# Proiect_TSC_v48.net
KiCad netlist of a schematic drawn in EAGLE
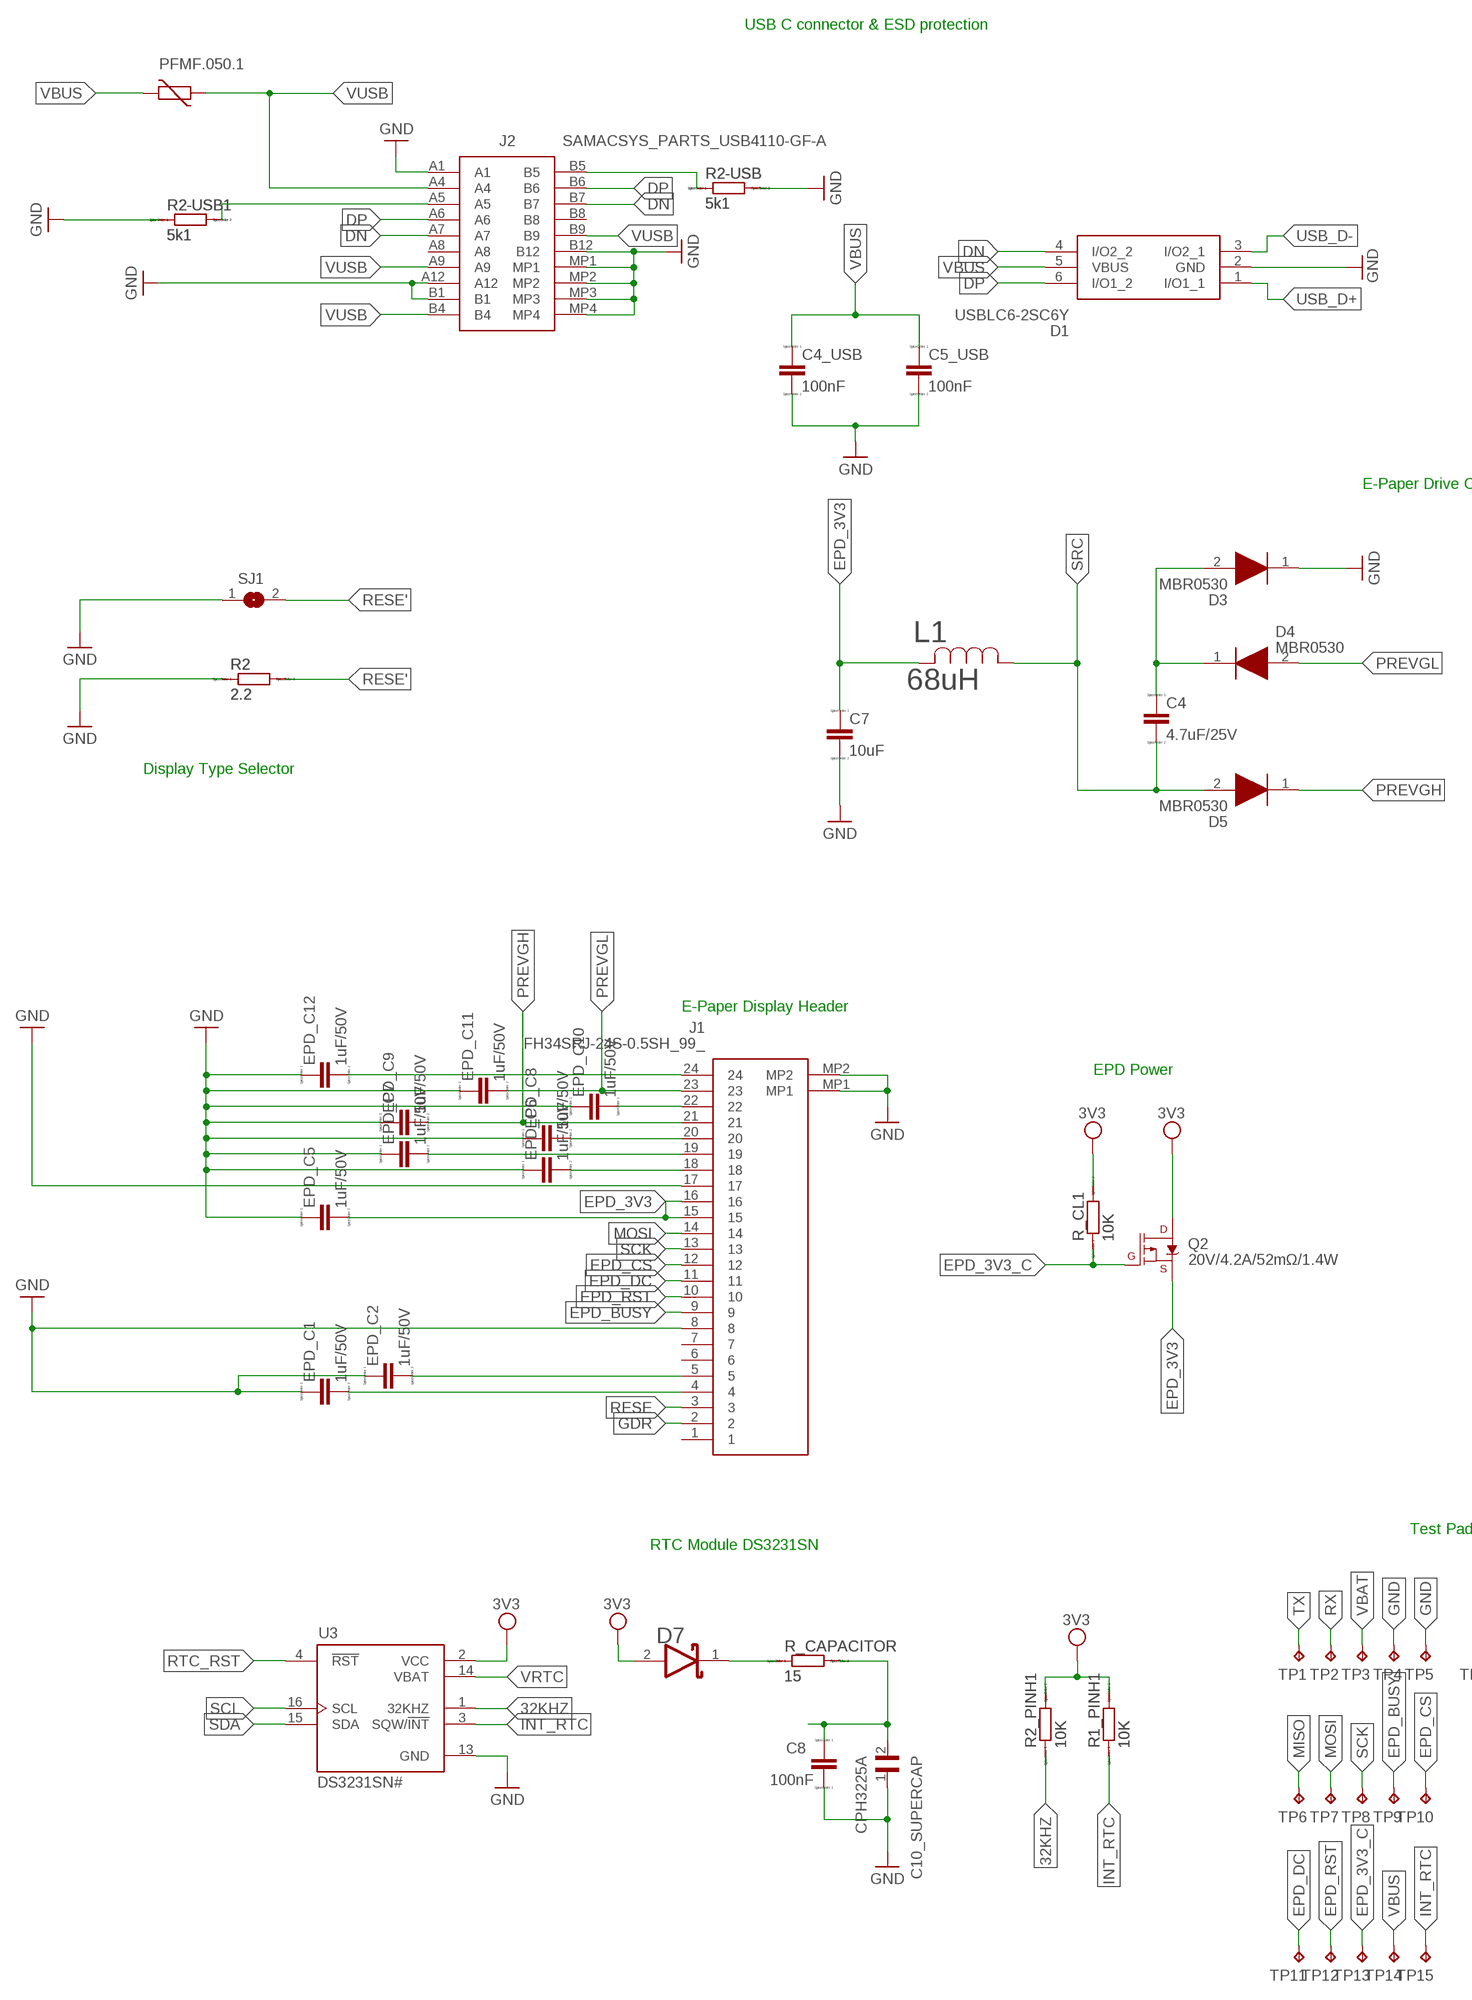
[diagram p0: schematic, sheet 1, part 1 of 2]
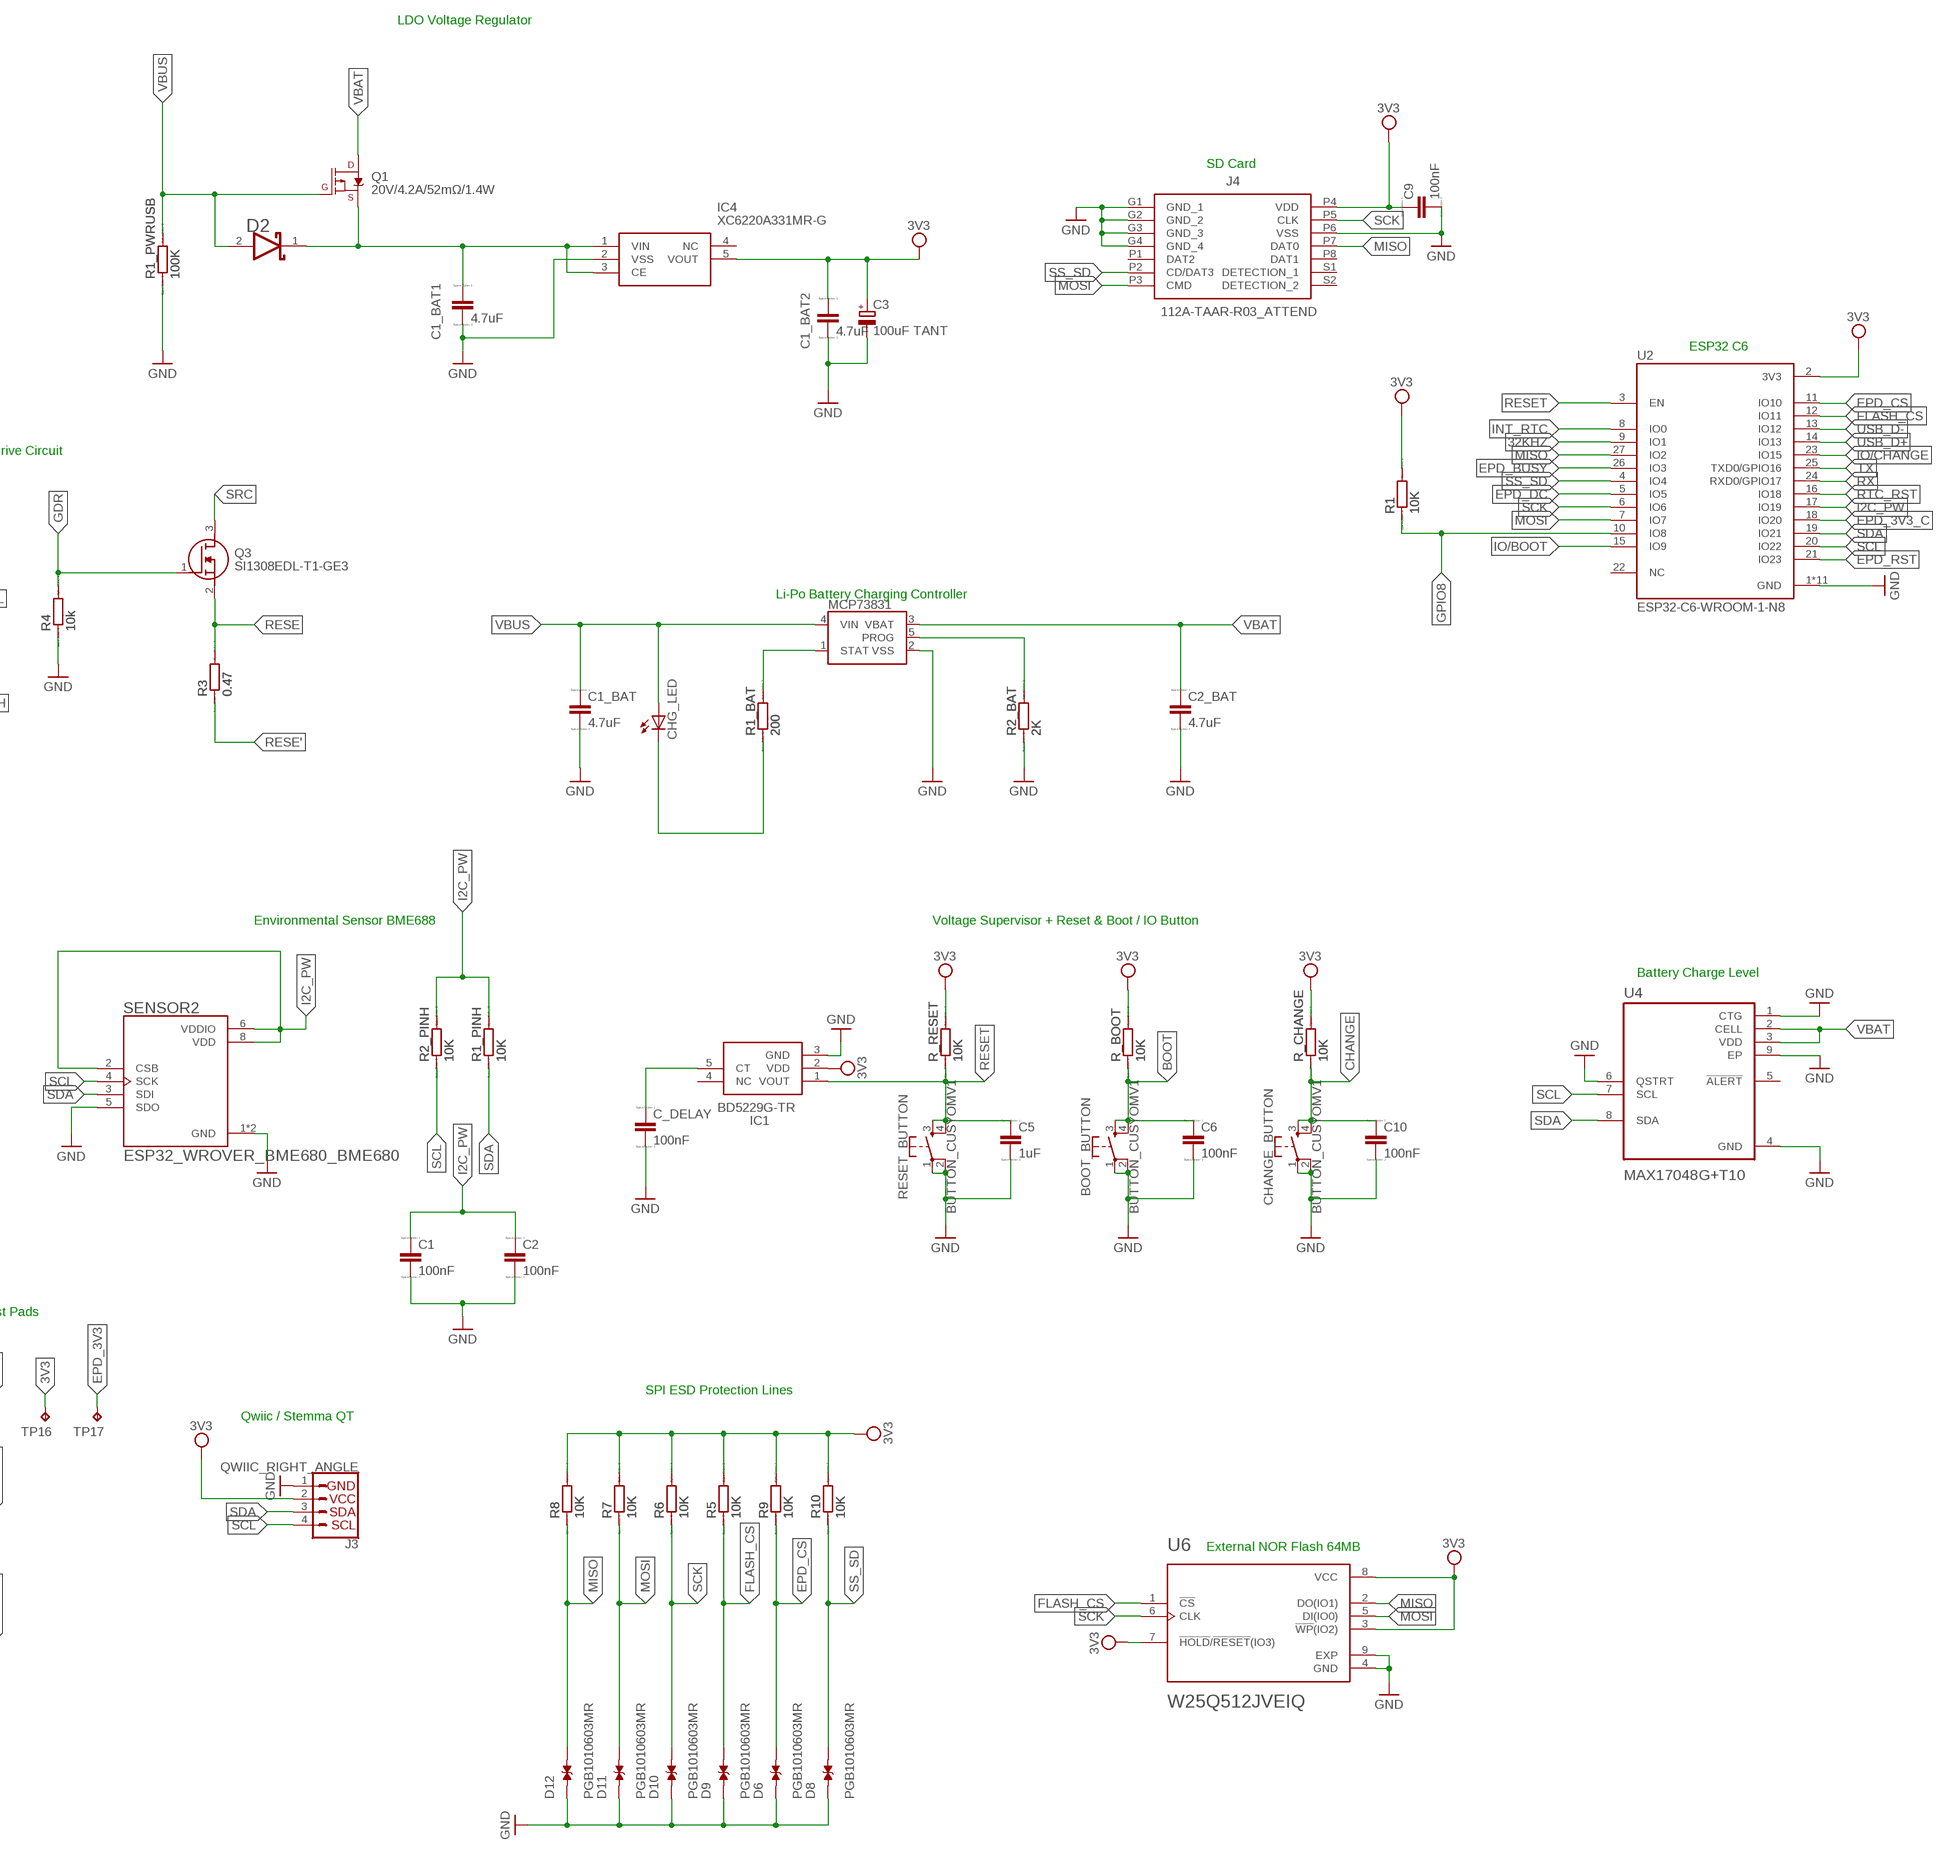
[diagram p1: schematic, sheet 1, part 2 of 2]

(export (version "E")
  (design (tool "Eeschema 10.0.6"))
  (components
    (comp (ref "BOOT_BUTTON")
      (value "BUTTON_CUSYOMV1")
      (footprint "eagle-import:MYBUTTON")
      (libsource (lib "eagle-import") (part "BUTTON_CUSYOMV1"))
    )
    (comp (ref "C1")
      (value "100nF")
      (footprint "eagle-import:ESP32_WROVER_EAGLE-LTSPICE_C0402")
      (libsource (lib "eagle-import") (part "ESP32_WROVER_EAGLE-LTSPICE_CC0402"))
    )
    (comp (ref "C1_BAT")
      (value "4.7uF")
      (footprint "eagle-import:ESP32_WROVER_EAGLE-LTSPICE_C0402")
      (libsource (lib "eagle-import") (part "ESP32_WROVER_EAGLE-LTSPICE_CC0402"))
    )
    (comp (ref "C1_BAT1")
      (value "4.7uF")
      (footprint "eagle-import:ESP32_WROVER_EAGLE-LTSPICE_C0402")
      (libsource (lib "eagle-import") (part "ESP32_WROVER_EAGLE-LTSPICE_CC0402"))
    )
    (comp (ref "C1_BAT2")
      (value "4.7uF")
      (footprint "eagle-import:ESP32_WROVER_EAGLE-LTSPICE_C0402")
      (libsource (lib "eagle-import") (part "ESP32_WROVER_EAGLE-LTSPICE_CC0402"))
    )
    (comp (ref "C2")
      (value "100nF")
      (footprint "eagle-import:ESP32_WROVER_EAGLE-LTSPICE_C0402")
      (libsource (lib "eagle-import") (part "ESP32_WROVER_EAGLE-LTSPICE_CC0402"))
    )
    (comp (ref "C2_BAT")
      (value "4.7uF")
      (footprint "eagle-import:ESP32_WROVER_EAGLE-LTSPICE_C0402")
      (libsource (lib "eagle-import") (part "ESP32_WROVER_EAGLE-LTSPICE_CC0402"))
    )
    (comp (ref "C3")
      (value "100uF TANT")
      (footprint "eagle-import:RCL_CT3528")
      (libsource (lib "eagle-import") (part "RCL_CPOL-EUCT3528"))
    )
    (comp (ref "C4")
      (value "4.7uF/25V")
      (footprint "eagle-import:ESP32_WROVER_EAGLE-LTSPICE_C0402")
      (libsource (lib "eagle-import") (part "ESP32_WROVER_EAGLE-LTSPICE_CC0402"))
    )
    (comp (ref "C4_USB")
      (value "100nF")
      (footprint "eagle-import:ESP32_WROVER_EAGLE-LTSPICE_C0402")
      (libsource (lib "eagle-import") (part "ESP32_WROVER_EAGLE-LTSPICE_CC0402"))
    )
    (comp (ref "C5")
      (value "1uF")
      (footprint "eagle-import:EAGLE-LTSPICE_C0402")
      (libsource (lib "eagle-import") (part "EAGLE-LTSPICE_CC0402"))
    )
    (comp (ref "C5_USB")
      (value "100nF")
      (footprint "eagle-import:ESP32_WROVER_EAGLE-LTSPICE_C0402")
      (libsource (lib "eagle-import") (part "ESP32_WROVER_EAGLE-LTSPICE_CC0402"))
    )
    (comp (ref "C6")
      (value "100nF")
      (footprint "eagle-import:EAGLE-LTSPICE_C0402")
      (libsource (lib "eagle-import") (part "EAGLE-LTSPICE_CC0402"))
    )
    (comp (ref "C7")
      (value "10uF")
      (footprint "eagle-import:EAGLE-LTSPICE_C0402")
      (libsource (lib "eagle-import") (part "EAGLE-LTSPICE_CC0402"))
    )
    (comp (ref "C8")
      (value "100nF")
      (footprint "eagle-import:EAGLE-LTSPICE_C0402")
      (libsource (lib "eagle-import") (part "EAGLE-LTSPICE_CC0402"))
    )
    (comp (ref "C9")
      (value "100nF")
      (footprint "eagle-import:ESP32_WROVER_EAGLE-LTSPICE_C0402")
      (libsource (lib "eagle-import") (part "ESP32_WROVER_EAGLE-LTSPICE_CC0402"))
    )
    (comp (ref "C10")
      (value "100nF")
      (footprint "eagle-import:EAGLE-LTSPICE_C0402")
      (libsource (lib "eagle-import") (part "EAGLE-LTSPICE_CC0402"))
    )
    (comp (ref "C10_SUPERCAP")
      (value "CPH3225A")
      (footprint "eagle-import:CAPCP3225X100N")
      (fields (field (name "MF") "Seiko Instruments"))
      (libsource (lib "eagle-import") (part "CPH3225A"))
    )
    (comp (ref "CHANGE_BUTTON")
      (value "BUTTON_CUSYOMV1")
      (footprint "eagle-import:MYBUTTON")
      (libsource (lib "eagle-import") (part "BUTTON_CUSYOMV1"))
    )
    (comp (ref "CHG_LED")
      (value "ADAFRUIT_LEDCHIP-LED0603")
      (footprint "eagle-import:ADAFRUIT_CHIP-LED0603")
      (libsource (lib "eagle-import") (part "ADAFRUIT_LEDCHIP-LED0603"))
    )
    (comp (ref "C_DELAY")
      (value "100nF")
      (footprint "eagle-import:EAGLE-LTSPICE_C0402")
      (libsource (lib "eagle-import") (part "EAGLE-LTSPICE_CC0402"))
    )
    (comp (ref "D1")
      (value "USBLC6-2SC6Y")
      (footprint "eagle-import:SOT95P280X145-6N")
      (fields (field (name "MF") "STMicroelectronics"))
      (libsource (lib "eagle-import") (part "USBLC6-2SC6Y"))
    )
    (comp (ref "D2")
      (value "ESP32_WROVER_AVX---SD0805S020S1R0_AVX_SD0805S020S1R0_0_0AVX_SD0805S020S1R0_0_0")
      (footprint "eagle-import:ESP32_WROVER_AVX---SD0805S020S1R0_AVX_SD0805S020S1R0_0")
      (fields
        (field (name "DIGIKEY_PART_NUMBER") "478-7800-1-ND")
        (field (name "MF") "AVX")
        (field (name "MOUSER_PART_NUMBER") "581-SD0805S020S1R0")
      )
      (libsource (lib "eagle-import") (part "ESP32_WROVER_AVX---SD0805S020S1R0_AVX_SD0805S020S1R0_0_0AVX_SD0805S020S1R0_0_0"))
    )
    (comp (ref "D3")
      (value "MBR0530")
      (footprint "eagle-import:SOD3716X135N")
      (fields (field (name "MF") "ON Semiconductor"))
      (libsource (lib "eagle-import") (part "MBR0530"))
    )
    (comp (ref "D4")
      (value "MBR0530")
      (footprint "eagle-import:SOD3716X135N")
      (fields (field (name "MF") "ON Semiconductor"))
      (libsource (lib "eagle-import") (part "MBR0530"))
    )
    (comp (ref "D5")
      (value "MBR0530")
      (footprint "eagle-import:SOD3716X135N")
      (fields (field (name "MF") "ON Semiconductor"))
      (libsource (lib "eagle-import") (part "MBR0530"))
    )
    (comp (ref "D6")
      (value "PGB1010603MR")
      (footprint "eagle-import:DIOC1608X36N")
      (fields (field (name "MF") "Littelfuse Inc."))
      (libsource (lib "eagle-import") (part "PGB1010603MR"))
    )
    (comp (ref "D7")
      (value "ESP32_WROVER_AVX---SD0805S020S1R0_AVX_SD0805S020S1R0_0_0AVX_SD0805S020S1R0_0_0")
      (footprint "eagle-import:ESP32_WROVER_AVX---SD0805S020S1R0_AVX_SD0805S020S1R0_0")
      (fields
        (field (name "DIGIKEY_PART_NUMBER") "478-7800-1-ND")
        (field (name "MF") "AVX")
        (field (name "MOUSER_PART_NUMBER") "581-SD0805S020S1R0")
      )
      (libsource (lib "eagle-import") (part "ESP32_WROVER_AVX---SD0805S020S1R0_AVX_SD0805S020S1R0_0_0AVX_SD0805S020S1R0_0_0"))
    )
    (comp (ref "D8")
      (value "PGB1010603MR")
      (footprint "eagle-import:DIOC1608X36N")
      (fields (field (name "MF") "Littelfuse Inc."))
      (libsource (lib "eagle-import") (part "PGB1010603MR"))
    )
    (comp (ref "D9")
      (value "PGB1010603MR")
      (footprint "eagle-import:DIOC1608X36N")
      (fields (field (name "MF") "Littelfuse Inc."))
      (libsource (lib "eagle-import") (part "PGB1010603MR"))
    )
    (comp (ref "D10")
      (value "PGB1010603MR")
      (footprint "eagle-import:DIOC1608X36N")
      (fields (field (name "MF") "Littelfuse Inc."))
      (libsource (lib "eagle-import") (part "PGB1010603MR"))
    )
    (comp (ref "D11")
      (value "PGB1010603MR")
      (footprint "eagle-import:DIOC1608X36N")
      (fields (field (name "MF") "Littelfuse Inc."))
      (libsource (lib "eagle-import") (part "PGB1010603MR"))
    )
    (comp (ref "D12")
      (value "PGB1010603MR")
      (footprint "eagle-import:DIOC1608X36N")
      (fields (field (name "MF") "Littelfuse Inc."))
      (libsource (lib "eagle-import") (part "PGB1010603MR"))
    )
    (comp (ref "EPD_C1")
      (value "1uF/50V")
      (footprint "eagle-import:ESP32_WROVER_EAGLE-LTSPICE_C0402")
      (libsource (lib "eagle-import") (part "ESP32_WROVER_EAGLE-LTSPICE_CC0402"))
    )
    (comp (ref "EPD_C2")
      (value "1uF/50V")
      (footprint "eagle-import:ESP32_WROVER_EAGLE-LTSPICE_C0402")
      (libsource (lib "eagle-import") (part "ESP32_WROVER_EAGLE-LTSPICE_CC0402"))
    )
    (comp (ref "EPD_C5")
      (value "1uF/50V")
      (footprint "eagle-import:ESP32_WROVER_EAGLE-LTSPICE_C0402")
      (libsource (lib "eagle-import") (part "ESP32_WROVER_EAGLE-LTSPICE_CC0402"))
    )
    (comp (ref "EPD_C6")
      (value "1uF/50V")
      (footprint "eagle-import:ESP32_WROVER_EAGLE-LTSPICE_C0402")
      (libsource (lib "eagle-import") (part "ESP32_WROVER_EAGLE-LTSPICE_CC0402"))
    )
    (comp (ref "EPD_C7")
      (value "1uF/50V")
      (footprint "eagle-import:ESP32_WROVER_EAGLE-LTSPICE_C0402")
      (libsource (lib "eagle-import") (part "ESP32_WROVER_EAGLE-LTSPICE_CC0402"))
    )
    (comp (ref "EPD_C8")
      (value "1uF/50V")
      (footprint "eagle-import:ESP32_WROVER_EAGLE-LTSPICE_C0402")
      (libsource (lib "eagle-import") (part "ESP32_WROVER_EAGLE-LTSPICE_CC0402"))
    )
    (comp (ref "EPD_C9")
      (value "1uF/50V")
      (footprint "eagle-import:ESP32_WROVER_EAGLE-LTSPICE_C0402")
      (libsource (lib "eagle-import") (part "ESP32_WROVER_EAGLE-LTSPICE_CC0402"))
    )
    (comp (ref "EPD_C10")
      (value "1uF/50V")
      (footprint "eagle-import:ESP32_WROVER_EAGLE-LTSPICE_C0402")
      (libsource (lib "eagle-import") (part "ESP32_WROVER_EAGLE-LTSPICE_CC0402"))
    )
    (comp (ref "EPD_C11")
      (value "1uF/50V")
      (footprint "eagle-import:ESP32_WROVER_EAGLE-LTSPICE_C0402")
      (libsource (lib "eagle-import") (part "ESP32_WROVER_EAGLE-LTSPICE_CC0402"))
    )
    (comp (ref "EPD_C12")
      (value "1uF/50V")
      (footprint "eagle-import:ESP32_WROVER_EAGLE-LTSPICE_C0402")
      (libsource (lib "eagle-import") (part "ESP32_WROVER_EAGLE-LTSPICE_CC0402"))
    )
    (comp (ref "IC1")
      (value "BD5229G-TR")
      (footprint "eagle-import:SOT95P280X125-5N")
      (fields (field (name "MOUSER_PART_NUMBER") "755-BD5229G-TR"))
      (libsource (lib "eagle-import") (part "BD5229G-TR"))
    )
    (comp (ref "IC4")
      (value "XC6220A331MR-G")
      (footprint "eagle-import:SOT95P280X120-5N")
      (fields (field (name "MOUSER_PART_NUMBER") "865-XC6220A331MR-G"))
      (libsource (lib "eagle-import") (part "XC6220A331MR-G"))
    )
    (comp (ref "J1")
      (value "FH34SRJ-24S-0.5SH_99_")
      (footprint "eagle-import:FH34SRJ24S05SH99")
      (fields
        (field (name "MANUFACTURER_PART_NUMBER") "FH34SRJ-24S-0.5SH(99)")
        (field (name "MOUSER_PART_NUMBER") "798-FH34SRJ24S05SH99")
      )
      (libsource (lib "eagle-import") (part "FH34SRJ-24S-0.5SH_99_"))
    )
    (comp (ref "J2")
      (value "SAMACSYS_PARTS_USB4110-GF-A")
      (footprint "eagle-import:SAMACSYS_PARTS_USB4110GFA")
      (fields
        (field (name "MANUFACTURER_PART_NUMBER") "USB4110-GF-A")
        (field (name "MOUSER_PART_NUMBER") "640-USB4110-GF-A")
      )
      (libsource (lib "eagle-import") (part "SAMACSYS_PARTS_USB4110-GF-A"))
    )
    (comp (ref "J3")
      (value "QWIIC_RIGHT_ANGLE")
      (footprint "eagle-import:JST04_1MM_RA")
      (libsource (lib "eagle-import") (part "QWIIC_CONNECTORJS-1MM"))
    )
    (comp (ref "J4")
      (value "112A-TAAR-R03_ATTEND")
      (footprint "eagle-import:112ATAARR03ATTEND")
      (fields (field (name "MANUFACTURER_PART_NUMBER") "112A-TAAR-R03 ATTEND"))
      (libsource (lib "eagle-import") (part "112A-TAAR-R03_ATTEND"))
    )
    (comp (ref "L1")
      (value "68uH")
      (footprint "eagle-import:IND_4828-WE-TPC_WRE")
      (fields
        (field (name "MANUFACTURER_PART_NUMBER") "744043680")
        (field (name "COPYRIGHT") "Copyright (C) 2024 Ultra Librarian. All rights reserved.")
      )
      (libsource (lib "eagle-import") (part "744043680IND_4828-WE-TPC_WRE"))
    )
    (comp (ref "MCP73831")
      (value "ESP32_WROVER_SPARKFUN-IC-POWER_MCP73831")
      (footprint "eagle-import:ESP32_WROVER_SPARKFUN-IC-POWER_SOT23-5")
      (libsource (lib "eagle-import") (part "ESP32_WROVER_SPARKFUN-IC-POWER_MCP73831"))
    )
    (comp (ref "PFMF.050.1")
      (value "ESP32C6_VARISTORCN1812")
      (footprint "eagle-import:ESP32C6_VARISTOR_CT_CN1812")
      (libsource (lib "eagle-import") (part "ESP32C6_VARISTORCN1812"))
    )
    (comp (ref "Q1")
      (value "20V/4.2A/52mΩ/1.4W")
      (footprint "eagle-import:ESP32_WROVER_SPARKFUN-DISCRETESEMI_SOT23-3")
      (libsource (lib "eagle-import") (part "ESP32_WROVER_SPARKFUN-DISCRETESEMI_MOSFET_PCH-DMG2305UX-7"))
    )
    (comp (ref "Q2")
      (value "20V/4.2A/52mΩ/1.4W")
      (footprint "eagle-import:ESP32_WROVER_SPARKFUN-DISCRETESEMI_SOT23-3")
      (libsource (lib "eagle-import") (part "ESP32_WROVER_SPARKFUN-DISCRETESEMI_MOSFET_PCH-DMG2305UX-7"))
    )
    (comp (ref "Q3")
      (value "SI1308EDL-T1-GE3")
      (footprint "eagle-import:SOT65P210X110-3N")
      (fields (field (name "MF") "Vishay Siliconix"))
      (libsource (lib "eagle-import") (part "SI1308EDL-T1-GE3"))
    )
    (comp (ref "R1")
      (value "10K")
      (footprint "eagle-import:ESP32_WROVER_EAGLE-LTSPICE_R0402")
      (libsource (lib "eagle-import") (part "ESP32_WROVER_EAGLE-LTSPICE_RR0402"))
    )
    (comp (ref "R1_BAT")
      (value "200")
      (footprint "eagle-import:ESP32_WROVER_EAGLE-LTSPICE_R0402")
      (libsource (lib "eagle-import") (part "ESP32_WROVER_EAGLE-LTSPICE_RR0402"))
    )
    (comp (ref "R1_PINH")
      (value "10K")
      (footprint "eagle-import:ESP32_WROVER_EAGLE-LTSPICE_R0402")
      (libsource (lib "eagle-import") (part "ESP32_WROVER_EAGLE-LTSPICE_RR0402"))
    )
    (comp (ref "R1_PINH1")
      (value "10K")
      (footprint "eagle-import:ESP32_WROVER_EAGLE-LTSPICE_R0402")
      (libsource (lib "eagle-import") (part "ESP32_WROVER_EAGLE-LTSPICE_RR0402"))
    )
    (comp (ref "R1_PWRUSB")
      (value "100K")
      (footprint "eagle-import:ESP32_WROVER_EAGLE-LTSPICE_R0402")
      (libsource (lib "eagle-import") (part "ESP32_WROVER_EAGLE-LTSPICE_RR0402"))
    )
    (comp (ref "R2")
      (value "2.2")
      (footprint "eagle-import:ESP32_WROVER_EAGLE-LTSPICE_R0402")
      (libsource (lib "eagle-import") (part "ESP32_WROVER_EAGLE-LTSPICE_RR0402"))
    )
    (comp (ref "R2-USB")
      (value "5k1")
      (footprint "eagle-import:ESP32_WROVER_EAGLE-LTSPICE_R0402")
      (libsource (lib "eagle-import") (part "ESP32_WROVER_EAGLE-LTSPICE_RR0402"))
    )
    (comp (ref "R2-USB1")
      (value "5k1")
      (footprint "eagle-import:ESP32_WROVER_EAGLE-LTSPICE_R0402")
      (libsource (lib "eagle-import") (part "ESP32_WROVER_EAGLE-LTSPICE_RR0402"))
    )
    (comp (ref "R2_BAT")
      (value "2K")
      (footprint "eagle-import:ESP32_WROVER_EAGLE-LTSPICE_R0402")
      (libsource (lib "eagle-import") (part "ESP32_WROVER_EAGLE-LTSPICE_RR0402"))
    )
    (comp (ref "R2_PINH")
      (value "10K")
      (footprint "eagle-import:ESP32_WROVER_EAGLE-LTSPICE_R0402")
      (libsource (lib "eagle-import") (part "ESP32_WROVER_EAGLE-LTSPICE_RR0402"))
    )
    (comp (ref "R2_PINH1")
      (value "10K")
      (footprint "eagle-import:ESP32_WROVER_EAGLE-LTSPICE_R0402")
      (libsource (lib "eagle-import") (part "ESP32_WROVER_EAGLE-LTSPICE_RR0402"))
    )
    (comp (ref "R3")
      (value "0.47")
      (footprint "eagle-import:ESP32_WROVER_EAGLE-LTSPICE_R0402")
      (libsource (lib "eagle-import") (part "ESP32_WROVER_EAGLE-LTSPICE_RR0402"))
    )
    (comp (ref "R4")
      (value "10k")
      (footprint "eagle-import:ESP32_WROVER_EAGLE-LTSPICE_R0402")
      (libsource (lib "eagle-import") (part "ESP32_WROVER_EAGLE-LTSPICE_RR0402"))
    )
    (comp (ref "R5")
      (value "10K")
      (footprint "eagle-import:ESP32_WROVER_EAGLE-LTSPICE_R0402")
      (libsource (lib "eagle-import") (part "ESP32_WROVER_EAGLE-LTSPICE_RR0402"))
    )
    (comp (ref "R6")
      (value "10K")
      (footprint "eagle-import:ESP32_WROVER_EAGLE-LTSPICE_R0402")
      (libsource (lib "eagle-import") (part "ESP32_WROVER_EAGLE-LTSPICE_RR0402"))
    )
    (comp (ref "R7")
      (value "10K")
      (footprint "eagle-import:ESP32_WROVER_EAGLE-LTSPICE_R0402")
      (libsource (lib "eagle-import") (part "ESP32_WROVER_EAGLE-LTSPICE_RR0402"))
    )
    (comp (ref "R8")
      (value "10K")
      (footprint "eagle-import:ESP32_WROVER_EAGLE-LTSPICE_R0402")
      (libsource (lib "eagle-import") (part "ESP32_WROVER_EAGLE-LTSPICE_RR0402"))
    )
    (comp (ref "R9")
      (value "10K")
      (footprint "eagle-import:ESP32_WROVER_EAGLE-LTSPICE_R0402")
      (libsource (lib "eagle-import") (part "ESP32_WROVER_EAGLE-LTSPICE_RR0402"))
    )
    (comp (ref "R10")
      (value "10K")
      (footprint "eagle-import:ESP32_WROVER_EAGLE-LTSPICE_R0402")
      (libsource (lib "eagle-import") (part "ESP32_WROVER_EAGLE-LTSPICE_RR0402"))
    )
    (comp (ref "RESET_BUTTON")
      (value "BUTTON_CUSYOMV1")
      (footprint "eagle-import:MYBUTTON")
      (libsource (lib "eagle-import") (part "BUTTON_CUSYOMV1"))
    )
    (comp (ref "R_BOOT")
      (value "10K")
      (footprint "eagle-import:ESP32_WROVER_EAGLE-LTSPICE_R0402")
      (libsource (lib "eagle-import") (part "ESP32_WROVER_EAGLE-LTSPICE_RR0402"))
    )
    (comp (ref "R_CAPACITOR")
      (value "15")
      (footprint "eagle-import:ESP32_WROVER_EAGLE-LTSPICE_R0402")
      (libsource (lib "eagle-import") (part "ESP32_WROVER_EAGLE-LTSPICE_RR0402"))
    )
    (comp (ref "R_CHANGE")
      (value "10K")
      (footprint "eagle-import:ESP32_WROVER_EAGLE-LTSPICE_R0402")
      (libsource (lib "eagle-import") (part "ESP32_WROVER_EAGLE-LTSPICE_RR0402"))
    )
    (comp (ref "R_CL1")
      (value "10K")
      (footprint "eagle-import:ESP32_WROVER_EAGLE-LTSPICE_R0402")
      (libsource (lib "eagle-import") (part "ESP32_WROVER_EAGLE-LTSPICE_RR0402"))
    )
    (comp (ref "R_RESET")
      (value "10K")
      (footprint "eagle-import:ESP32_WROVER_EAGLE-LTSPICE_R0402")
      (libsource (lib "eagle-import") (part "ESP32_WROVER_EAGLE-LTSPICE_RR0402"))
    )
    (comp (ref "SENSOR2")
      (value "ESP32_WROVER_BME680_BME680")
      (footprint "eagle-import:ESP32_WROVER_BME680_PSON80P300X300X100-8N")
      (fields (field (name "MF") "Bosch Sensortec") (field (name "MP") "BME680"))
      (libsource (lib "eagle-import") (part "ESP32_WROVER_BME680_BME680"))
    )
    (comp (ref "SJ1") (value "SJ") (footprint "eagle-import:SJ") (libsource (lib "eagle-import") (part "SJ")))
    (comp (ref "TP1")
      (value "TPTP20R")
      (footprint "eagle-import:TP20R")
      (libsource (lib "eagle-import") (part "TPTP20R"))
    )
    (comp (ref "TP2")
      (value "TPTP20R")
      (footprint "eagle-import:TP20R")
      (libsource (lib "eagle-import") (part "TPTP20R"))
    )
    (comp (ref "TP3")
      (value "TPTP20R")
      (footprint "eagle-import:TP20R")
      (libsource (lib "eagle-import") (part "TPTP20R"))
    )
    (comp (ref "TP4")
      (value "TPTP20R")
      (footprint "eagle-import:TP20R")
      (libsource (lib "eagle-import") (part "TPTP20R"))
    )
    (comp (ref "TP5")
      (value "TPTP20R")
      (footprint "eagle-import:TP20R")
      (libsource (lib "eagle-import") (part "TPTP20R"))
    )
    (comp (ref "TP6")
      (value "TPTP20R")
      (footprint "eagle-import:TP20R")
      (libsource (lib "eagle-import") (part "TPTP20R"))
    )
    (comp (ref "TP7")
      (value "TPTP20R")
      (footprint "eagle-import:TP20R")
      (libsource (lib "eagle-import") (part "TPTP20R"))
    )
    (comp (ref "TP8")
      (value "TPTP20R")
      (footprint "eagle-import:TP20R")
      (libsource (lib "eagle-import") (part "TPTP20R"))
    )
    (comp (ref "TP9")
      (value "TPTP20R")
      (footprint "eagle-import:TP20R")
      (libsource (lib "eagle-import") (part "TPTP20R"))
    )
    (comp (ref "TP10")
      (value "TPTP20R")
      (footprint "eagle-import:TP20R")
      (libsource (lib "eagle-import") (part "TPTP20R"))
    )
    (comp (ref "TP11")
      (value "TPTP20R")
      (footprint "eagle-import:TP20R")
      (libsource (lib "eagle-import") (part "TPTP20R"))
    )
    (comp (ref "TP12")
      (value "TPTP20R")
      (footprint "eagle-import:TP20R")
      (libsource (lib "eagle-import") (part "TPTP20R"))
    )
    (comp (ref "TP13")
      (value "TPTP20R")
      (footprint "eagle-import:TP20R")
      (libsource (lib "eagle-import") (part "TPTP20R"))
    )
    (comp (ref "TP14")
      (value "TPTP20R")
      (footprint "eagle-import:TP20R")
      (libsource (lib "eagle-import") (part "TPTP20R"))
    )
    (comp (ref "TP15")
      (value "TPTP20R")
      (footprint "eagle-import:TP20R")
      (libsource (lib "eagle-import") (part "TPTP20R"))
    )
    (comp (ref "TP16")
      (value "TPTP20R")
      (footprint "eagle-import:TP20R")
      (libsource (lib "eagle-import") (part "TPTP20R"))
    )
    (comp (ref "TP17")
      (value "TPTP20R")
      (footprint "eagle-import:TP20R")
      (libsource (lib "eagle-import") (part "TPTP20R"))
    )
    (comp (ref "U2")
      (value "ESP32-C6-WROOM-1-N8")
      (footprint "eagle-import:XCVR_ESP32-C6-WROOM-1-N8")
      (fields (field (name "MF") "Espressif Systems"))
      (libsource (lib "eagle-import") (part "ESP32-C6-WROOM-1-N8"))
    )
    (comp (ref "U3")
      (value "DS3231SN#")
      (footprint "eagle-import:SOIC127P1032X265-16N")
      (fields (field (name "MF") "Analog Devices"))
      (libsource (lib "eagle-import") (part "DS3231SN#"))
    )
    (comp (ref "U4")
      (value "MAX17048G+T10")
      (footprint "eagle-import:SON50P200X200X80-9N")
      (fields (field (name "MF") "Analog Devices"))
      (libsource (lib "eagle-import") (part "MAX17048G+T10"))
    )
    (comp (ref "U6")
      (value "W25Q512JVEIQ")
      (footprint "eagle-import:SON127P600X800X80-9N")
      (fields (field (name "MF") "Winbond Electronics"))
      (libsource (lib "eagle-import") (part "W25Q512JVEIQ"))
    )
  )
  (nets
    (net (code "1") (name "3V3") (class "Default")
      (node (ref "C1_BAT2") (pin "1") (pinfunction "1_1") (pintype "passive"))
      (node (ref "C3") (pin "+") (pinfunction "+_+") (pintype "passive"))
      (node (ref "C9") (pin "1") (pinfunction "1_1") (pintype "passive"))
      (node (ref "D7") (pin "2") (pinfunction "ANODE_2") (pintype "bidirectional"))
      (node (ref "IC1") (pin "2") (pinfunction "VDD_2") (pintype "bidirectional"))
      (node (ref "IC4") (pin "5") (pinfunction "VOUT_5") (pintype "bidirectional"))
      (node (ref "J3") (pin "2") (pinfunction "2_2") (pintype "power_in"))
      (node (ref "J4") (pin "P4") (pinfunction "VDD_P4") (pintype "bidirectional"))
      (node (ref "Q2") (pin "3") (pinfunction "D_3") (pintype "bidirectional"))
      (node (ref "R1") (pin "2") (pinfunction "2_2") (pintype "passive"))
      (node (ref "R10") (pin "2") (pinfunction "2_2") (pintype "passive"))
      (node (ref "R1_PINH1") (pin "2") (pinfunction "2_2") (pintype "passive"))
      (node (ref "R2_PINH1") (pin "2") (pinfunction "2_2") (pintype "passive"))
      (node (ref "R5") (pin "2") (pinfunction "2_2") (pintype "passive"))
      (node (ref "R6") (pin "2") (pinfunction "2_2") (pintype "passive"))
      (node (ref "R7") (pin "2") (pinfunction "2_2") (pintype "passive"))
      (node (ref "R8") (pin "2") (pinfunction "2_2") (pintype "passive"))
      (node (ref "R9") (pin "2") (pinfunction "2_2") (pintype "passive"))
      (node (ref "R_BOOT") (pin "2") (pinfunction "2_2") (pintype "passive"))
      (node (ref "R_CHANGE") (pin "2") (pinfunction "2_2") (pintype "passive"))
      (node (ref "R_CL1") (pin "2") (pinfunction "2_2") (pintype "passive"))
      (node (ref "R_RESET") (pin "2") (pinfunction "2_2") (pintype "passive"))
      (node (ref "TP16") (pin "TP") (pinfunction "TP_TP") (pintype "input"))
      (node (ref "U2") (pin "2") (pinfunction "3V3_2") (pintype "power_in"))
      (node (ref "U3") (pin "2") (pinfunction "VCC_2") (pintype "power_in"))
      (node (ref "U6") (pin "3") (pinfunction "~{WP}(IO2)_3") (pintype "bidirectional"))
      (node (ref "U6") (pin "7") (pinfunction "~{HOLD}/~{RESET}(IO3)_7") (pintype "bidirectional"))
      (node (ref "U6") (pin "8") (pinfunction "VCC_8") (pintype "power_in"))
    )
    (net (code "2") (name "32KHZ") (class "Default")
      (node (ref "R2_PINH1") (pin "1") (pinfunction "1_1") (pintype "passive"))
      (node (ref "U2") (pin "9") (pinfunction "IO1_9") (pintype "bidirectional"))
      (node (ref "U3") (pin "1") (pinfunction "32KHZ_1") (pintype "output"))
    )
    (net (code "3") (name "BOOT") (class "Default")
      (node (ref "BOOT_BUTTON") (pin "3") (pinfunction "3_3") (pintype "passive"))
      (node (ref "BOOT_BUTTON") (pin "4") (pinfunction "4_4") (pintype "passive"))
      (node (ref "C6") (pin "1") (pinfunction "1_1") (pintype "passive"))
      (node (ref "R_BOOT") (pin "1") (pinfunction "1_1") (pintype "passive"))
    )
    (net (code "4") (name "CHANGE") (class "Default")
      (node (ref "C10") (pin "1") (pinfunction "1_1") (pintype "passive"))
      (node (ref "CHANGE_BUTTON") (pin "3") (pinfunction "3_3") (pintype "passive"))
      (node (ref "CHANGE_BUTTON") (pin "4") (pinfunction "4_4") (pintype "passive"))
      (node (ref "R_CHANGE") (pin "1") (pinfunction "1_1") (pintype "passive"))
    )
    (net (code "5") (name "DN") (class "Default")
      (node (ref "D1") (pin "4") (pinfunction "I/O2_2_4") (pintype "bidirectional"))
      (node (ref "J2") (pin "A7") (pinfunction "A7_A7") (pintype "bidirectional"))
      (node (ref "J2") (pin "B7") (pinfunction "B7_B7") (pintype "bidirectional"))
    )
    (net (code "6") (name "DP") (class "Default")
      (node (ref "D1") (pin "6") (pinfunction "I/O1_2_6") (pintype "bidirectional"))
      (node (ref "J2") (pin "A6") (pinfunction "A6_A6") (pintype "bidirectional"))
      (node (ref "J2") (pin "B6") (pinfunction "B6_B6") (pintype "bidirectional"))
    )
    (net (code "7") (name "EPD_3V3") (class "Default")
      (node (ref "C7") (pin "1") (pinfunction "1_1") (pintype "passive"))
      (node (ref "EPD_C5") (pin "2") (pinfunction "2_2") (pintype "passive"))
      (node (ref "J1") (pin "15") (pinfunction "15_15") (pintype "bidirectional"))
      (node (ref "J1") (pin "16") (pinfunction "16_16") (pintype "bidirectional"))
      (node (ref "L1") (pin "2") (pinfunction "2_2") (pintype "passive"))
      (node (ref "Q2") (pin "2") (pinfunction "S_2") (pintype "bidirectional"))
      (node (ref "TP17") (pin "TP") (pinfunction "TP_TP") (pintype "input"))
    )
    (net (code "8") (name "EPD_3V3_C") (class "Default")
      (node (ref "Q2") (pin "1") (pinfunction "G_1") (pintype "bidirectional"))
      (node (ref "R_CL1") (pin "1") (pinfunction "1_1") (pintype "passive"))
      (node (ref "TP13") (pin "TP") (pinfunction "TP_TP") (pintype "input"))
      (node (ref "U2") (pin "18") (pinfunction "IO20_18") (pintype "bidirectional"))
    )
    (net (code "9") (name "EPD_BUSY") (class "Default")
      (node (ref "J1") (pin "9") (pinfunction "9_9") (pintype "bidirectional"))
      (node (ref "TP9") (pin "TP") (pinfunction "TP_TP") (pintype "input"))
      (node (ref "U2") (pin "26") (pinfunction "IO3_26") (pintype "bidirectional"))
    )
    (net (code "10") (name "EPD_CS") (class "Default")
      (node (ref "D6") (pin "2") (pinfunction "2_2") (pintype "passive"))
      (node (ref "J1") (pin "12") (pinfunction "12_12") (pintype "bidirectional"))
      (node (ref "R9") (pin "1") (pinfunction "1_1") (pintype "passive"))
      (node (ref "TP10") (pin "TP") (pinfunction "TP_TP") (pintype "input"))
      (node (ref "U2") (pin "11") (pinfunction "IO10_11") (pintype "bidirectional"))
    )
    (net (code "11") (name "EPD_DC") (class "Default")
      (node (ref "J1") (pin "11") (pinfunction "11_11") (pintype "bidirectional"))
      (node (ref "TP11") (pin "TP") (pinfunction "TP_TP") (pintype "input"))
      (node (ref "U2") (pin "5") (pinfunction "IO5_5") (pintype "bidirectional"))
    )
    (net (code "12") (name "EPD_RST") (class "Default")
      (node (ref "J1") (pin "10") (pinfunction "10_10") (pintype "bidirectional"))
      (node (ref "TP12") (pin "TP") (pinfunction "TP_TP") (pintype "input"))
      (node (ref "U2") (pin "21") (pinfunction "IO23_21") (pintype "bidirectional"))
    )
    (net (code "13") (name "FLASH_CS") (class "Default")
      (node (ref "D9") (pin "2") (pinfunction "2_2") (pintype "passive"))
      (node (ref "R5") (pin "1") (pinfunction "1_1") (pintype "passive"))
      (node (ref "U2") (pin "12") (pinfunction "IO11_12") (pintype "bidirectional"))
      (node (ref "U6") (pin "1") (pinfunction "~{CS}_1") (pintype "input"))
    )
    (net (code "14") (name "GDR") (class "Default")
      (node (ref "J1") (pin "2") (pinfunction "2_2") (pintype "bidirectional"))
      (node (ref "Q3") (pin "1") (pinfunction "G_1") (pintype "bidirectional"))
      (node (ref "R4") (pin "2") (pinfunction "2_2") (pintype "passive"))
    )
    (net (code "15") (name "GND") (class "Default")
      (node (ref "BOOT_BUTTON") (pin "1") (pinfunction "1_1") (pintype "passive"))
      (node (ref "BOOT_BUTTON") (pin "2") (pinfunction "2_2") (pintype "passive"))
      (node (ref "C1") (pin "2") (pinfunction "2_2") (pintype "passive"))
      (node (ref "C10") (pin "2") (pinfunction "2_2") (pintype "passive"))
      (node (ref "C10_SUPERCAP") (pin "1") (pinfunction "1_1") (pintype "passive"))
      (node (ref "C1_BAT") (pin "2") (pinfunction "2_2") (pintype "passive"))
      (node (ref "C1_BAT1") (pin "2") (pinfunction "2_2") (pintype "passive"))
      (node (ref "C1_BAT2") (pin "2") (pinfunction "2_2") (pintype "passive"))
      (node (ref "C2") (pin "2") (pinfunction "2_2") (pintype "passive"))
      (node (ref "C2_BAT") (pin "2") (pinfunction "2_2") (pintype "passive"))
      (node (ref "C3") (pin "-") (pinfunction "-_-") (pintype "passive"))
      (node (ref "C4_USB") (pin "2") (pinfunction "2_2") (pintype "passive"))
      (node (ref "C5") (pin "2") (pinfunction "2_2") (pintype "passive"))
      (node (ref "C5_USB") (pin "2") (pinfunction "2_2") (pintype "passive"))
      (node (ref "C6") (pin "2") (pinfunction "2_2") (pintype "passive"))
      (node (ref "C7") (pin "2") (pinfunction "2_2") (pintype "passive"))
      (node (ref "C8") (pin "2") (pinfunction "2_2") (pintype "passive"))
      (node (ref "C9") (pin "2") (pinfunction "2_2") (pintype "passive"))
      (node (ref "CHANGE_BUTTON") (pin "1") (pinfunction "1_1") (pintype "passive"))
      (node (ref "CHANGE_BUTTON") (pin "2") (pinfunction "2_2") (pintype "passive"))
      (node (ref "C_DELAY") (pin "2") (pinfunction "2_2") (pintype "passive"))
      (node (ref "D1") (pin "2") (pinfunction "GND_2") (pintype "bidirectional"))
      (node (ref "D10") (pin "1") (pinfunction "1_1") (pintype "passive"))
      (node (ref "D11") (pin "1") (pinfunction "1_1") (pintype "passive"))
      (node (ref "D12") (pin "1") (pinfunction "1_1") (pintype "passive"))
      (node (ref "D3") (pin "1") (pinfunction "K_1") (pintype "bidirectional"))
      (node (ref "D6") (pin "1") (pinfunction "1_1") (pintype "passive"))
      (node (ref "D8") (pin "1") (pinfunction "1_1") (pintype "passive"))
      (node (ref "D9") (pin "1") (pinfunction "1_1") (pintype "passive"))
      (node (ref "EPD_C1") (pin "1") (pinfunction "1_1") (pintype "passive"))
      (node (ref "EPD_C10") (pin "1") (pinfunction "1_1") (pintype "passive"))
      (node (ref "EPD_C11") (pin "1") (pinfunction "1_1") (pintype "passive"))
      (node (ref "EPD_C12") (pin "1") (pinfunction "1_1") (pintype "passive"))
      (node (ref "EPD_C2") (pin "1") (pinfunction "1_1") (pintype "passive"))
      (node (ref "EPD_C5") (pin "1") (pinfunction "1_1") (pintype "passive"))
      (node (ref "EPD_C6") (pin "1") (pinfunction "1_1") (pintype "passive"))
      (node (ref "EPD_C7") (pin "1") (pinfunction "1_1") (pintype "passive"))
      (node (ref "EPD_C8") (pin "1") (pinfunction "1_1") (pintype "passive"))
      (node (ref "EPD_C9") (pin "1") (pinfunction "1_1") (pintype "passive"))
      (node (ref "IC1") (pin "3") (pinfunction "GND_3") (pintype "bidirectional"))
      (node (ref "IC4") (pin "2") (pinfunction "VSS_2") (pintype "bidirectional"))
      (node (ref "J1") (pin "17") (pinfunction "17_17") (pintype "bidirectional"))
      (node (ref "J1") (pin "8") (pinfunction "8_8") (pintype "bidirectional"))
      (node (ref "J1") (pin "MP1") (pinfunction "MP1_MP1") (pintype "bidirectional"))
      (node (ref "J1") (pin "MP2") (pinfunction "MP2_MP2") (pintype "bidirectional"))
      (node (ref "J2") (pin "A1") (pinfunction "A1_A1") (pintype "bidirectional"))
      (node (ref "J2") (pin "A12") (pinfunction "A12_A12") (pintype "bidirectional"))
      (node (ref "J2") (pin "B1") (pinfunction "B1_B1") (pintype "bidirectional"))
      (node (ref "J2") (pin "B12") (pinfunction "B12_B12") (pintype "bidirectional"))
      (node (ref "J2") (pin "MP1") (pinfunction "MP1_MP1") (pintype "bidirectional"))
      (node (ref "J2") (pin "MP2") (pinfunction "MP2_MP2") (pintype "bidirectional"))
      (node (ref "J2") (pin "MP3") (pinfunction "MP3_MP3") (pintype "bidirectional"))
      (node (ref "J2") (pin "MP4") (pinfunction "MP4_MP4") (pintype "bidirectional"))
      (node (ref "J3") (pin "1") (pinfunction "1_1") (pintype "power_in"))
      (node (ref "J4") (pin "G1") (pinfunction "GND_1_G1") (pintype "bidirectional"))
      (node (ref "J4") (pin "G2") (pinfunction "GND_2_G2") (pintype "bidirectional"))
      (node (ref "J4") (pin "G3") (pinfunction "GND_3_G3") (pintype "bidirectional"))
      (node (ref "J4") (pin "G4") (pinfunction "GND_4_G4") (pintype "bidirectional"))
      (node (ref "J4") (pin "P6") (pinfunction "VSS_P6") (pintype "bidirectional"))
      (node (ref "MCP73831") (pin "2") (pinfunction "VSS_2") (pintype "power_in"))
      (node (ref "R1_PWRUSB") (pin "1") (pinfunction "1_1") (pintype "passive"))
      (node (ref "R2") (pin "1") (pinfunction "1_1") (pintype "passive"))
      (node (ref "R2-USB") (pin "2") (pinfunction "2_2") (pintype "passive"))
      (node (ref "R2-USB1") (pin "1") (pinfunction "1_1") (pintype "passive"))
      (node (ref "R2_BAT") (pin "1") (pinfunction "1_1") (pintype "passive"))
      (node (ref "R4") (pin "1") (pinfunction "1_1") (pintype "passive"))
      (node (ref "RESET_BUTTON") (pin "1") (pinfunction "1_1") (pintype "passive"))
      (node (ref "RESET_BUTTON") (pin "2") (pinfunction "2_2") (pintype "passive"))
      (node (ref "SENSOR2") (pin "1") (pinfunction "GND_1") (pintype "power_in"))
      (node (ref "SENSOR2") (pin "5") (pinfunction "SDO_5") (pintype "bidirectional"))
      (node (ref "SENSOR2") (pin "7") (pinfunction "GND_7") (pintype "power_in"))
      (node (ref "SJ1") (pin "1") (pinfunction "1_1") (pintype "passive"))
      (node (ref "TP4") (pin "TP") (pinfunction "TP_TP") (pintype "input"))
      (node (ref "TP5") (pin "TP") (pinfunction "TP_TP") (pintype "input"))
      (node (ref "U2") (pin "1") (pinfunction "GND_1") (pintype "power_in"))
      (node (ref "U2") (pin "28") (pinfunction "GND_28") (pintype "power_in"))
      (node (ref "U2") (pin "29_1") (pinfunction "GND_29_1") (pintype "power_in"))
      (node (ref "U2") (pin "29_2") (pinfunction "GND_29_2") (pintype "power_in"))
      (node (ref "U2") (pin "29_3") (pinfunction "GND_29_3") (pintype "power_in"))
      (node (ref "U2") (pin "29_4") (pinfunction "GND_29_4") (pintype "power_in"))
      (node (ref "U2") (pin "29_5") (pinfunction "GND_29_5") (pintype "power_in"))
      (node (ref "U2") (pin "29_6") (pinfunction "GND_29_6") (pintype "power_in"))
      (node (ref "U2") (pin "29_7") (pinfunction "GND_29_7") (pintype "power_in"))
      (node (ref "U2") (pin "29_8") (pinfunction "GND_29_8") (pintype "power_in"))
      (node (ref "U2") (pin "29_9") (pinfunction "GND_29_9") (pintype "power_in"))
      (node (ref "U3") (pin "13") (pinfunction "GND_13") (pintype "power_in"))
      (node (ref "U4") (pin "1") (pinfunction "CTG_1") (pintype "power_in"))
      (node (ref "U4") (pin "4") (pinfunction "GND_4") (pintype "power_in"))
      (node (ref "U4") (pin "6") (pinfunction "QSTRT_6") (pintype "input"))
      (node (ref "U4") (pin "9") (pinfunction "EP_9") (pintype "power_in"))
      (node (ref "U6") (pin "4") (pinfunction "GND_4") (pintype "power_in"))
      (node (ref "U6") (pin "9") (pinfunction "EXP_9") (pintype "passive"))
    )
    (net (code "16") (name "GPIO8") (class "Default")
      (node (ref "R1") (pin "1") (pinfunction "1_1") (pintype "passive"))
      (node (ref "U2") (pin "10") (pinfunction "IO8_10") (pintype "bidirectional"))
    )
    (net (code "17") (name "I2C_PW") (class "Default")
      (node (ref "C1") (pin "1") (pinfunction "1_1") (pintype "passive"))
      (node (ref "C2") (pin "1") (pinfunction "1_1") (pintype "passive"))
      (node (ref "R1_PINH") (pin "2") (pinfunction "2_2") (pintype "passive"))
      (node (ref "R2_PINH") (pin "2") (pinfunction "2_2") (pintype "passive"))
      (node (ref "SENSOR2") (pin "2") (pinfunction "CSB_2") (pintype "input"))
      (node (ref "SENSOR2") (pin "6") (pinfunction "VDDIO_6") (pintype "power_in"))
      (node (ref "SENSOR2") (pin "8") (pinfunction "VDD_8") (pintype "power_in"))
      (node (ref "U2") (pin "17") (pinfunction "IO19_17") (pintype "bidirectional"))
    )
    (net (code "18") (name "INT_RTC") (class "Default")
      (node (ref "R1_PINH1") (pin "1") (pinfunction "1_1") (pintype "passive"))
      (node (ref "TP15") (pin "TP") (pinfunction "TP_TP") (pintype "input"))
      (node (ref "U2") (pin "8") (pinfunction "IO0_8") (pintype "bidirectional"))
      (node (ref "U3") (pin "3") (pinfunction "SQW/~{INT}_3") (pintype "output"))
    )
    (net (code "19") (name "IO{slash}BOOT") (class "Default")
      (node (ref "U2") (pin "15") (pinfunction "IO9_15") (pintype "bidirectional"))
    )
    (net (code "20") (name "IO{slash}CHANGE") (class "Default")
      (node (ref "U2") (pin "23") (pinfunction "IO15_23") (pintype "bidirectional"))
    )
    (net (code "21") (name "MISO") (class "Default")
      (node (ref "D12") (pin "2") (pinfunction "2_2") (pintype "passive"))
      (node (ref "J4") (pin "P7") (pinfunction "DAT0_P7") (pintype "bidirectional"))
      (node (ref "R8") (pin "1") (pinfunction "1_1") (pintype "passive"))
      (node (ref "TP6") (pin "TP") (pinfunction "TP_TP") (pintype "input"))
      (node (ref "U2") (pin "27") (pinfunction "IO2_27") (pintype "bidirectional"))
      (node (ref "U6") (pin "2") (pinfunction "DO(IO1)_2") (pintype "bidirectional"))
    )
    (net (code "22") (name "MOSI") (class "Default")
      (node (ref "D11") (pin "2") (pinfunction "2_2") (pintype "passive"))
      (node (ref "J1") (pin "14") (pinfunction "14_14") (pintype "bidirectional"))
      (node (ref "J4") (pin "P3") (pinfunction "CMD_P3") (pintype "bidirectional"))
      (node (ref "R7") (pin "1") (pinfunction "1_1") (pintype "passive"))
      (node (ref "TP7") (pin "TP") (pinfunction "TP_TP") (pintype "input"))
      (node (ref "U2") (pin "7") (pinfunction "IO7_7") (pintype "bidirectional"))
      (node (ref "U6") (pin "5") (pinfunction "DI(IO0)_5") (pintype "bidirectional"))
    )
    (net (code "23") (name "Net-(C10_SUPERCAP-Pad2)") (class "Default")
      (node (ref "C10_SUPERCAP") (pin "2") (pinfunction "2_2") (pintype "passive"))
      (node (ref "C8") (pin "1") (pinfunction "1_1") (pintype "passive"))
      (node (ref "R_CAPACITOR") (pin "2") (pinfunction "2_2") (pintype "passive"))
    )
    (net (code "24") (name "Net-(CHG_LED-PadC)") (class "Default")
      (node (ref "CHG_LED") (pin "C") (pinfunction "C_C") (pintype "passive"))
      (node (ref "R1_BAT") (pin "1") (pinfunction "1_1") (pintype "passive"))
    )
    (net (code "25") (name "Net-(D2-CATHODE)") (class "Default")
      (node (ref "C1_BAT1") (pin "1") (pinfunction "1_1") (pintype "passive"))
      (node (ref "D2") (pin "1") (pinfunction "CATHODE_1") (pintype "bidirectional"))
      (node (ref "IC4") (pin "1") (pinfunction "VIN_1") (pintype "bidirectional"))
      (node (ref "IC4") (pin "3") (pinfunction "CE_3") (pintype "bidirectional"))
      (node (ref "Q1") (pin "2") (pinfunction "S_2") (pintype "bidirectional"))
    )
    (net (code "26") (name "Net-(D3-A)") (class "Default")
      (node (ref "C4") (pin "1") (pinfunction "1_1") (pintype "passive"))
      (node (ref "D3") (pin "2") (pinfunction "A_2") (pintype "bidirectional"))
      (node (ref "D4") (pin "1") (pinfunction "K_1") (pintype "bidirectional"))
    )
    (net (code "27") (name "Net-(D7-CATHODE)") (class "Default")
      (node (ref "D7") (pin "1") (pinfunction "CATHODE_1") (pintype "bidirectional"))
      (node (ref "R_CAPACITOR") (pin "1") (pinfunction "1_1") (pintype "passive"))
    )
    (net (code "28") (name "Net-(EPD_C1-Pad2)") (class "Default")
      (node (ref "EPD_C1") (pin "2") (pinfunction "2_2") (pintype "passive"))
      (node (ref "J1") (pin "4") (pinfunction "4_4") (pintype "bidirectional"))
    )
    (net (code "29") (name "Net-(EPD_C2-Pad2)") (class "Default")
      (node (ref "EPD_C2") (pin "2") (pinfunction "2_2") (pintype "passive"))
      (node (ref "J1") (pin "5") (pinfunction "5_5") (pintype "bidirectional"))
    )
    (net (code "30") (name "Net-(EPD_C6-Pad2)") (class "Default")
      (node (ref "EPD_C6") (pin "2") (pinfunction "2_2") (pintype "passive"))
      (node (ref "J1") (pin "18") (pinfunction "18_18") (pintype "bidirectional"))
    )
    (net (code "31") (name "Net-(EPD_C7-Pad2)") (class "Default")
      (node (ref "EPD_C7") (pin "2") (pinfunction "2_2") (pintype "passive"))
      (node (ref "J1") (pin "19") (pinfunction "19_19") (pintype "bidirectional"))
    )
    (net (code "32") (name "Net-(EPD_C8-Pad2)") (class "Default")
      (node (ref "EPD_C8") (pin "2") (pinfunction "2_2") (pintype "passive"))
      (node (ref "J1") (pin "20") (pinfunction "20_20") (pintype "bidirectional"))
    )
    (net (code "33") (name "Net-(EPD_C10-Pad2)") (class "Default")
      (node (ref "EPD_C10") (pin "2") (pinfunction "2_2") (pintype "passive"))
      (node (ref "J1") (pin "22") (pinfunction "22_22") (pintype "bidirectional"))
    )
    (net (code "34") (name "Net-(EPD_C12-Pad2)") (class "Default")
      (node (ref "EPD_C12") (pin "2") (pinfunction "2_2") (pintype "passive"))
      (node (ref "J1") (pin "24") (pinfunction "24_24") (pintype "bidirectional"))
    )
    (net (code "35") (name "Net-(IC1-CT)") (class "Default")
      (node (ref "C_DELAY") (pin "1") (pinfunction "1_1") (pintype "passive"))
      (node (ref "IC1") (pin "5") (pinfunction "CT_5") (pintype "bidirectional"))
    )
    (net (code "36") (name "Net-(J2-PadA5)") (class "Default")
      (node (ref "J2") (pin "A5") (pinfunction "A5_A5") (pintype "bidirectional"))
      (node (ref "R2-USB1") (pin "2") (pinfunction "2_2") (pintype "passive"))
    )
    (net (code "37") (name "Net-(J2-PadB5)") (class "Default")
      (node (ref "J2") (pin "B5") (pinfunction "B5_B5") (pintype "bidirectional"))
      (node (ref "R2-USB") (pin "1") (pinfunction "1_1") (pintype "passive"))
    )
    (net (code "38") (name "Net-(MCP73831-PROG)") (class "Default")
      (node (ref "MCP73831") (pin "5") (pinfunction "PROG_5") (pintype "input"))
      (node (ref "R2_BAT") (pin "2") (pinfunction "2_2") (pintype "passive"))
    )
    (net (code "39") (name "Net-(MCP73831-STAT)") (class "Default")
      (node (ref "MCP73831") (pin "1") (pinfunction "STAT_1") (pintype "output"))
      (node (ref "R1_BAT") (pin "2") (pinfunction "2_2") (pintype "passive"))
    )
    (net (code "40") (name "PREVGH") (class "Default")
      (node (ref "D5") (pin "1") (pinfunction "K_1") (pintype "bidirectional"))
      (node (ref "EPD_C9") (pin "2") (pinfunction "2_2") (pintype "passive"))
      (node (ref "J1") (pin "21") (pinfunction "21_21") (pintype "bidirectional"))
    )
    (net (code "41") (name "PREVGL") (class "Default")
      (node (ref "D4") (pin "2") (pinfunction "A_2") (pintype "bidirectional"))
      (node (ref "EPD_C11") (pin "2") (pinfunction "2_2") (pintype "passive"))
      (node (ref "J1") (pin "23") (pinfunction "23_23") (pintype "bidirectional"))
    )
    (net (code "42") (name "RESE") (class "Default")
      (node (ref "J1") (pin "3") (pinfunction "3_3") (pintype "bidirectional"))
      (node (ref "Q3") (pin "2") (pinfunction "S_2") (pintype "bidirectional"))
      (node (ref "R3") (pin "2") (pinfunction "2_2") (pintype "passive"))
    )
    (net (code "43") (name "RESE'") (class "Default")
      (node (ref "R2") (pin "2") (pinfunction "2_2") (pintype "passive"))
      (node (ref "R3") (pin "1") (pinfunction "1_1") (pintype "passive"))
      (node (ref "SJ1") (pin "2") (pinfunction "2_2") (pintype "passive"))
    )
    (net (code "44") (name "RESET") (class "Default")
      (node (ref "C5") (pin "1") (pinfunction "1_1") (pintype "passive"))
      (node (ref "IC1") (pin "1") (pinfunction "VOUT_1") (pintype "bidirectional"))
      (node (ref "RESET_BUTTON") (pin "3") (pinfunction "3_3") (pintype "passive"))
      (node (ref "RESET_BUTTON") (pin "4") (pinfunction "4_4") (pintype "passive"))
      (node (ref "R_RESET") (pin "1") (pinfunction "1_1") (pintype "passive"))
      (node (ref "U2") (pin "3") (pinfunction "EN_3") (pintype "input"))
    )
    (net (code "45") (name "RTC_RST") (class "Default")
      (node (ref "U2") (pin "16") (pinfunction "IO18_16") (pintype "bidirectional"))
      (node (ref "U3") (pin "4") (pinfunction "~{RST}_4") (pintype "input"))
    )
    (net (code "46") (name "RX") (class "Default")
      (node (ref "TP2") (pin "TP") (pinfunction "TP_TP") (pintype "input"))
      (node (ref "U2") (pin "24") (pinfunction "RXD0/GPIO17_24") (pintype "bidirectional"))
    )
    (net (code "47") (name "SCK") (class "Default")
      (node (ref "D10") (pin "2") (pinfunction "2_2") (pintype "passive"))
      (node (ref "J1") (pin "13") (pinfunction "13_13") (pintype "bidirectional"))
      (node (ref "J4") (pin "P5") (pinfunction "CLK_P5") (pintype "bidirectional"))
      (node (ref "R6") (pin "1") (pinfunction "1_1") (pintype "passive"))
      (node (ref "TP8") (pin "TP") (pinfunction "TP_TP") (pintype "input"))
      (node (ref "U2") (pin "6") (pinfunction "IO6_6") (pintype "bidirectional"))
      (node (ref "U6") (pin "6") (pinfunction "CLK_6") (pintype "input"))
    )
    (net (code "48") (name "SCL") (class "Default")
      (node (ref "J3") (pin "4") (pinfunction "4_4") (pintype "passive"))
      (node (ref "R2_PINH") (pin "1") (pinfunction "1_1") (pintype "passive"))
      (node (ref "SENSOR2") (pin "4") (pinfunction "SCK_4") (pintype "input"))
      (node (ref "U2") (pin "20") (pinfunction "IO22_20") (pintype "bidirectional"))
      (node (ref "U3") (pin "16") (pinfunction "SCL_16") (pintype "input"))
      (node (ref "U4") (pin "7") (pinfunction "SCL_7") (pintype "input"))
    )
    (net (code "49") (name "SDA") (class "Default")
      (node (ref "J3") (pin "3") (pinfunction "3_3") (pintype "passive"))
      (node (ref "R1_PINH") (pin "1") (pinfunction "1_1") (pintype "passive"))
      (node (ref "SENSOR2") (pin "3") (pinfunction "SDI_3") (pintype "bidirectional"))
      (node (ref "U2") (pin "19") (pinfunction "IO21_19") (pintype "bidirectional"))
      (node (ref "U3") (pin "15") (pinfunction "SDA_15") (pintype "bidirectional"))
      (node (ref "U4") (pin "8") (pinfunction "SDA_8") (pintype "bidirectional"))
    )
    (net (code "50") (name "SRC") (class "Default")
      (node (ref "C4") (pin "2") (pinfunction "2_2") (pintype "passive"))
      (node (ref "D5") (pin "2") (pinfunction "A_2") (pintype "bidirectional"))
      (node (ref "L1") (pin "1") (pinfunction "1_1") (pintype "passive"))
      (node (ref "Q3") (pin "3") (pinfunction "D_3") (pintype "bidirectional"))
    )
    (net (code "51") (name "SS_SD") (class "Default")
      (node (ref "D8") (pin "2") (pinfunction "2_2") (pintype "passive"))
      (node (ref "J4") (pin "P2") (pinfunction "CD/DAT3_P2") (pintype "bidirectional"))
      (node (ref "R10") (pin "1") (pinfunction "1_1") (pintype "passive"))
      (node (ref "U2") (pin "4") (pinfunction "IO4_4") (pintype "bidirectional"))
    )
    (net (code "52") (name "TX") (class "Default")
      (node (ref "TP1") (pin "TP") (pinfunction "TP_TP") (pintype "input"))
      (node (ref "U2") (pin "25") (pinfunction "TXD0/GPIO16_25") (pintype "bidirectional"))
    )
    (net (code "53") (name "USB_D+") (class "Default")
      (node (ref "D1") (pin "1") (pinfunction "I/O1_1_1") (pintype "bidirectional"))
      (node (ref "U2") (pin "14") (pinfunction "IO13_14") (pintype "bidirectional"))
    )
    (net (code "54") (name "USB_D-") (class "Default")
      (node (ref "D1") (pin "3") (pinfunction "I/O2_1_3") (pintype "bidirectional"))
      (node (ref "U2") (pin "13") (pinfunction "IO12_13") (pintype "bidirectional"))
    )
    (net (code "55") (name "VBAT") (class "Default")
      (node (ref "C2_BAT") (pin "1") (pinfunction "1_1") (pintype "passive"))
      (node (ref "MCP73831") (pin "3") (pinfunction "VBAT_3") (pintype "power_in"))
      (node (ref "Q1") (pin "3") (pinfunction "D_3") (pintype "bidirectional"))
      (node (ref "TP3") (pin "TP") (pinfunction "TP_TP") (pintype "input"))
      (node (ref "U4") (pin "2") (pinfunction "CELL_2") (pintype "power_in"))
      (node (ref "U4") (pin "3") (pinfunction "VDD_3") (pintype "power_in"))
    )
    (net (code "56") (name "VBUS") (class "Default")
      (node (ref "C1_BAT") (pin "1") (pinfunction "1_1") (pintype "passive"))
      (node (ref "C4_USB") (pin "1") (pinfunction "1_1") (pintype "passive"))
      (node (ref "C5_USB") (pin "1") (pinfunction "1_1") (pintype "passive"))
      (node (ref "CHG_LED") (pin "A") (pinfunction "A_A") (pintype "passive"))
      (node (ref "D1") (pin "5") (pinfunction "VBUS_5") (pintype "bidirectional"))
      (node (ref "D2") (pin "2") (pinfunction "ANODE_2") (pintype "bidirectional"))
      (node (ref "MCP73831") (pin "4") (pinfunction "VIN_4") (pintype "power_in"))
      (node (ref "PFMF.050.1") (pin "2") (pinfunction "2_2") (pintype "passive"))
      (node (ref "Q1") (pin "1") (pinfunction "G_1") (pintype "bidirectional"))
      (node (ref "R1_PWRUSB") (pin "2") (pinfunction "2_2") (pintype "passive"))
      (node (ref "TP14") (pin "TP") (pinfunction "TP_TP") (pintype "input"))
    )
    (net (code "57") (name "VRTC") (class "Default")
      (node (ref "U3") (pin "14") (pinfunction "VBAT_14") (pintype "power_in"))
    )
    (net (code "58") (name "VUSB") (class "Default")
      (node (ref "J2") (pin "A4") (pinfunction "A4_A4") (pintype "bidirectional"))
      (node (ref "J2") (pin "A9") (pinfunction "A9_A9") (pintype "bidirectional"))
      (node (ref "J2") (pin "B4") (pinfunction "B4_B4") (pintype "bidirectional"))
      (node (ref "J2") (pin "B9") (pinfunction "B9_B9") (pintype "bidirectional"))
      (node (ref "PFMF.050.1") (pin "1") (pinfunction "1_1") (pintype "passive"))
    )
    (net (code "59") (name "unconnected-(IC1-NC-Pad4)") (class "Default")
      (node (ref "IC1") (pin "4") (pinfunction "NC_4") (pintype "no_connect"))
    )
    (net (code "60") (name "unconnected-(IC4-NC-Pad4)") (class "Default")
      (node (ref "IC4") (pin "4") (pinfunction "NC_4") (pintype "no_connect"))
    )
    (net (code "61") (name "unconnected-(J1-Pad1)") (class "Default")
      (node (ref "J1") (pin "1") (pinfunction "1_1") (pintype "bidirectional"))
    )
    (net (code "62") (name "unconnected-(J1-Pad6)") (class "Default")
      (node (ref "J1") (pin "6") (pinfunction "6_6") (pintype "bidirectional"))
    )
    (net (code "63") (name "unconnected-(J1-Pad7)") (class "Default")
      (node (ref "J1") (pin "7") (pinfunction "7_7") (pintype "bidirectional"))
    )
    (net (code "64") (name "unconnected-(J2-PadA8)") (class "Default")
      (node (ref "J2") (pin "A8") (pinfunction "A8_A8") (pintype "bidirectional"))
    )
    (net (code "65") (name "unconnected-(J2-PadB8)") (class "Default")
      (node (ref "J2") (pin "B8") (pinfunction "B8_B8") (pintype "bidirectional"))
    )
    (net (code "66") (name "unconnected-(J4-DAT1-PadP8)") (class "Default")
      (node (ref "J4") (pin "P8") (pinfunction "DAT1_P8") (pintype "bidirectional"))
    )
    (net (code "67") (name "unconnected-(J4-DAT2-PadP1)") (class "Default")
      (node (ref "J4") (pin "P1") (pinfunction "DAT2_P1") (pintype "bidirectional"))
    )
    (net (code "68") (name "unconnected-(J4-DETECTION_1-PadS1)") (class "Default")
      (node (ref "J4") (pin "S1") (pinfunction "DETECTION_1_S1") (pintype "bidirectional"))
    )
    (net (code "69") (name "unconnected-(J4-DETECTION_2-PadS2)") (class "Default")
      (node (ref "J4") (pin "S2") (pinfunction "DETECTION_2_S2") (pintype "bidirectional"))
    )
    (net (code "70") (name "unconnected-(U2-NC-Pad22)") (class "Default")
      (node (ref "U2") (pin "22") (pinfunction "NC_22") (pintype "no_connect"))
    )
    (net (code "71") (name "unconnected-(U4-~{ALERT}-Pad5)") (class "Default")
      (node (ref "U4") (pin "5") (pinfunction "~{ALERT}_5") (pintype "output"))
    )
  )
)
